# Power_Breakout.net
KiCad netlist of a schematic drawn in Altium Designer
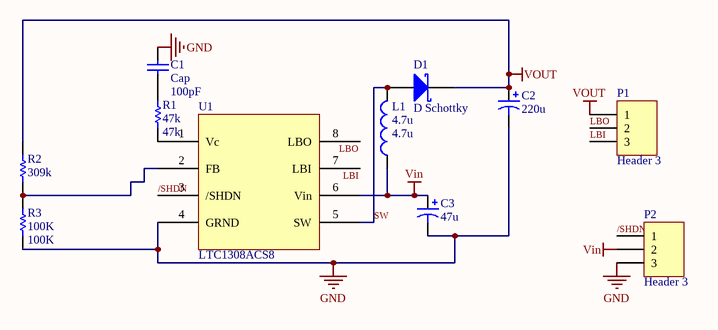
[diagram p0: Power_Breakout.SchDoc]

(export (version "E")
  (design (tool "Eeschema 10.0.6"))
  (components
    (comp (ref "C1")
      (value "Cap")
      (footprint "C0805")
      (description "Capacitor")
      (fields (field (name "ALTIUM_VALUE") "100pF") (field (name "PUBLISHER") "Altium Limited"))
      (libsource (lib "Miscellaneous Devices") (part "Cap"))
    )
    (comp (ref "C2")
      (value "220u")
      (footprint "C2917")
      (description "Polarized Capacitor (Radial)")
      (fields (field (name "PUBLISHER") "Altium Limited"))
      (libsource (lib "Miscellaneous Devices") (part "Cap Pol1"))
    )
    (comp (ref "C3")
      (value "47u")
      (footprint "C2312")
      (description "Polarized Capacitor (Radial)")
      (fields (field (name "PUBLISHER") "Altium Limited"))
      (libsource (lib "Miscellaneous Devices") (part "Cap Pol1"))
    )
    (comp (ref "D1")
      (value "D Schottky")
      (footprint "ShottkeyDiode")
      (description "Schottky Diode")
      (fields (field (name "PUBLISHER") "Altium Limited"))
      (libsource (lib "Miscellaneous Devices") (part "D Schottky"))
    )
    (comp (ref "L1")
      (value "4.7u")
      (footprint "Inductor")
      (description "Inductor")
      (fields (field (name "ALTIUM_VALUE") "4.7u") (field (name "PUBLISHER") "Altium Limited"))
      (libsource (lib "Miscellaneous Devices") (part "Inductor"))
    )
    (comp (ref "P1")
      (value "Header 3")
      (footprint "HDR1X3")
      (description "Header, 3-Pin")
      (fields (field (name "PUBLISHER") "Altium Limited"))
      (libsource (lib "Miscellaneous Connectors") (part "Header 3"))
    )
    (comp (ref "P2")
      (value "Header 3")
      (footprint "HDR1X3")
      (description "Header, 3-Pin")
      (fields (field (name "PUBLISHER") "Altium Limited"))
      (libsource (lib "Miscellaneous Connectors") (part "Header 3"))
    )
    (comp (ref "R1")
      (value "47k")
      (footprint "6-0805_M")
      (description "Resistor")
      (fields (field (name "ALTIUM_VALUE") "47k") (field (name "PUBLISHER") "Altium Limited"))
      (libsource (lib "Miscellaneous Devices") (part "Res1"))
    )
    (comp (ref "R2")
      (value "309k")
      (footprint "6-0805_M")
      (description "Resistor")
      (fields (field (name "PUBLISHER") "Altium Limited"))
      (libsource (lib "Miscellaneous Devices") (part "Res1"))
    )
    (comp (ref "R3")
      (value "100K")
      (footprint "6-0805_M")
      (description "Resistor")
      (fields (field (name "ALTIUM_VALUE") "100K") (field (name "PUBLISHER") "Altium Limited"))
      (libsource (lib "Miscellaneous Devices") (part "Res1"))
    )
    (comp (ref "U1")
      (value "LTC1308ACS8")
      (footprint "SOP8_LTC1308A")
      (libsource (lib "GameMan") (part "LTC1308ACS8"))
    )
  )
  (nets
    (net (code "1") (name "/LBI") (class "Default")
      (node (ref "P1") (pin "3") (pinfunction "3_3") (pintype "passive"))
      (node (ref "U1") (pin "7") (pinfunction "LBI_7") (pintype "power_in"))
    )
    (net (code "2") (name "/LBO") (class "Default")
      (node (ref "P1") (pin "2") (pinfunction "2_2") (pintype "passive"))
      (node (ref "U1") (pin "8") (pinfunction "LBO_8") (pintype "power_in"))
    )
    (net (code "3") (name "/SW") (class "Default")
      (node (ref "D1") (pin "A") (pinfunction "A_A") (pintype "passive"))
      (node (ref "L1") (pin "2") (pinfunction "2_2") (pintype "passive"))
      (node (ref "U1") (pin "5") (pinfunction "SW_5") (pintype "power_in"))
    )
    (net (code "4") (name "/{slash}SHDN") (class "Default")
      (node (ref "P2") (pin "1") (pinfunction "1_1") (pintype "passive"))
      (node (ref "U1") (pin "3") (pinfunction "/SHDN_3") (pintype "power_in"))
    )
    (net (code "5") (name "GND") (class "Default")
      (node (ref "C1") (pin "1") (pinfunction "1_1") (pintype "passive"))
      (node (ref "C2") (pin "2") (pinfunction "2_2") (pintype "passive"))
      (node (ref "C3") (pin "2") (pinfunction "2_2") (pintype "passive"))
      (node (ref "P2") (pin "3") (pinfunction "3_3") (pintype "passive"))
      (node (ref "R3") (pin "2") (pinfunction "2_2") (pintype "passive"))
      (node (ref "U1") (pin "4") (pinfunction "GRND_4") (pintype "power_in"))
    )
    (net (code "6") (name "Net-(C1-Pad2)") (class "Default")
      (node (ref "C1") (pin "2") (pinfunction "2_2") (pintype "passive"))
      (node (ref "R1") (pin "2") (pinfunction "2_2") (pintype "passive"))
    )
    (net (code "7") (name "Net-(U1-FB)") (class "Default")
      (node (ref "R2") (pin "2") (pinfunction "2_2") (pintype "passive"))
      (node (ref "R3") (pin "1") (pinfunction "1_1") (pintype "passive"))
      (node (ref "U1") (pin "2") (pinfunction "FB_2") (pintype "power_in"))
    )
    (net (code "8") (name "Net-(U1-Vc)") (class "Default")
      (node (ref "R1") (pin "1") (pinfunction "1_1") (pintype "passive"))
      (node (ref "U1") (pin "1") (pinfunction "Vc_1") (pintype "power_in"))
    )
    (net (code "9") (name "VOUT") (class "Default")
      (node (ref "C2") (pin "1") (pinfunction "1_1") (pintype "passive"))
      (node (ref "D1") (pin "K") (pinfunction "K_K") (pintype "passive"))
      (node (ref "P1") (pin "1") (pinfunction "1_1") (pintype "passive"))
      (node (ref "R2") (pin "1") (pinfunction "1_1") (pintype "passive"))
    )
    (net (code "10") (name "Vin") (class "Default")
      (node (ref "C3") (pin "1") (pinfunction "1_1") (pintype "passive"))
      (node (ref "L1") (pin "1") (pinfunction "1_1") (pintype "passive"))
      (node (ref "P2") (pin "2") (pinfunction "2_2") (pintype "passive"))
      (node (ref "U1") (pin "6") (pinfunction "Vin_6") (pintype "power_in"))
    )
  )
)
